# 03_pushswitch.net
KiCad netlist of a schematic drawn in Altium Designer
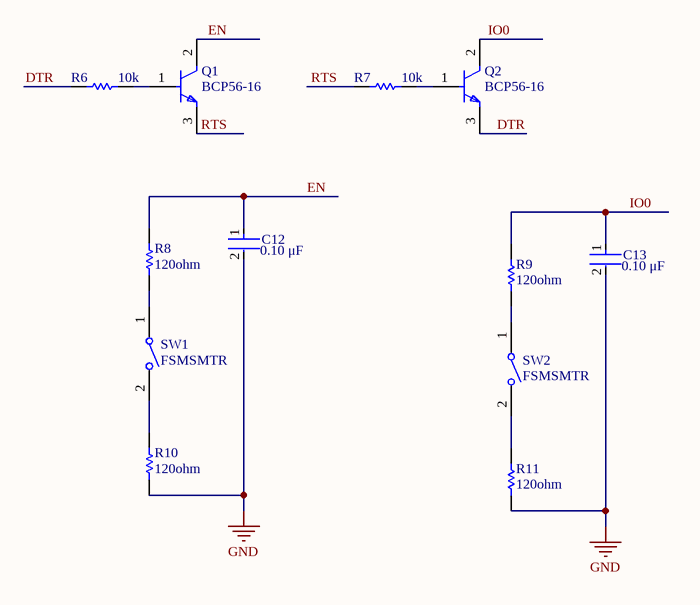
[diagram p0: 03_pushswitch.SchDoc]

(export (version "E")
  (design (tool "Eeschema 10.0.6"))
  (components
    (comp (ref "C12")
      (value "C0603C104M4RAC7411")
      (footprint "FP-C0603C-CF-MFG")
      (description "CAP CER 0.1UF 16V X7R 0603")
      (fields
        (field (name "TOLERANCE") "0.2")
        (field (name "CAPACITANCE") "0.10 μF")
        (field (name "MANUFACTURER") "KEMET")
      )
      (libsource (lib "Altium Content Vault") (part "b4654b650e69147ec39a6b967a45e02"))
    )
    (comp (ref "C13")
      (value "C0603C104M4RAC7411")
      (footprint "FP-C0603C-CF-MFG")
      (description "CAP CER 0.1UF 16V X7R 0603")
      (fields
        (field (name "TOLERANCE") "0.2")
        (field (name "CAPACITANCE") "0.10 μF")
        (field (name "MANUFACTURER") "KEMET")
      )
      (libsource (lib "Altium Content Vault") (part "b4654b650e69147ec39a6b967a45e02"))
    )
    (comp (ref "Q1")
      (value "BCP56-16")
      (footprint "FP-SOT-223-P008-MFG")
      (description "TRANS NPN 80V 1A SOT-223")
      (fields
        (field (name "OCTOPART") "https://octopart.com/bcp56-16-stmicroelectronics-13883839")
        (field (name "MANUFACTURER") "STMicroelectronics")
      )
      (libsource (lib "Altium Content Vault") (part "1c57d9dae74fe2702546667b0e849db"))
    )
    (comp (ref "Q2")
      (value "BCP56-16")
      (footprint "FP-SOT-223-P008-MFG")
      (description "TRANS NPN 80V 1A SOT-223")
      (fields
        (field (name "OCTOPART") "https://octopart.com/bcp56-16-stmicroelectronics-13883839")
        (field (name "MANUFACTURER") "STMicroelectronics")
      )
      (libsource (lib "Altium Content Vault") (part "1c57d9dae74fe2702546667b0e849db"))
    )
    (comp (ref "R6")
      (value "10k")
      (footprint "RESC1609X55X30LL15T15")
      (description "Chip Resistor, 10 KOhm, +/- 1%, 0.1 W, -55 to 155 degC, 0603 (1608 Metric), RoHS, Tape and Reel")
      (fields (field (name "TOLERANCE") "1%") (field (name "MANUFACTURER") "Panasonic"))
      (libsource (lib "Altium Content Vault") (part "RES-2"))
    )
    (comp (ref "R7")
      (value "10k")
      (footprint "RESC1609X55X30LL15T15")
      (description "Chip Resistor, 10 KOhm, +/- 1%, 0.1 W, -55 to 155 degC, 0603 (1608 Metric), RoHS, Tape and Reel")
      (fields (field (name "TOLERANCE") "1%") (field (name "MANUFACTURER") "Panasonic"))
      (libsource (lib "Altium Content Vault") (part "RES-2"))
    )
    (comp (ref "R8")
      (value "120ohm")
      (footprint "RESC1608X55X30NL20T20")
      (fields (field (name "PART NUMBER") "ERA-3AEB121V") (field (name "MANUFACTURER") "Panasonic"))
      (libsource (lib "Altium Content Vault") (part "RES"))
    )
    (comp (ref "R9")
      (value "120ohm")
      (footprint "RESC1608X55X30NL20T20")
      (fields (field (name "PART NUMBER") "ERA-3AEB121V") (field (name "MANUFACTURER") "Panasonic"))
      (libsource (lib "Altium Content Vault") (part "RES"))
    )
    (comp (ref "R10")
      (value "120ohm")
      (footprint "RESC1608X55X30NL20T20")
      (fields (field (name "PART NUMBER") "ERA-3AEB121V") (field (name "MANUFACTURER") "Panasonic"))
      (libsource (lib "Altium Content Vault") (part "RES"))
    )
    (comp (ref "R11")
      (value "120ohm")
      (footprint "RESC1608X55X30NL20T20")
      (fields (field (name "PART NUMBER") "ERA-3AEB121V") (field (name "MANUFACTURER") "Panasonic"))
      (libsource (lib "Altium Content Vault") (part "RES"))
    )
    (comp (ref "SW1")
      (value "FSMSMTR")
      (footprint "TECO-FSMSMTR_V")
      (description "FSMSM Push Button Switch, 50 mA, -35 to 85 degC, 2-Pin SMD, RoHS, Tape and Reel")
      (fields (field (name "MANUFACTURER") "TE Connectivity"))
      (libsource (lib "Altium Content Vault") (part "SW-SPST-2_C"))
    )
    (comp (ref "SW2")
      (value "FSMSMTR")
      (footprint "TECO-FSMSMTR_V")
      (description "FSMSM Push Button Switch, 50 mA, -35 to 85 degC, 2-Pin SMD, RoHS, Tape and Reel")
      (fields (field (name "MANUFACTURER") "TE Connectivity"))
      (libsource (lib "Altium Content Vault") (part "SW-SPST-2_C"))
    )
  )
  (nets
    (net (code "1") (name "/DTR") (class "Default")
      (node (ref "Q2") (pin "3") (pinfunction "E_3") (pintype "passive"))
      (node (ref "R6") (pin "1") (pinfunction "1_1") (pintype "passive"))
    )
    (net (code "2") (name "/EN") (class "Default")
      (node (ref "C12") (pin "1") (pinfunction "1_1") (pintype "passive"))
      (node (ref "Q1") (pin "2") (pinfunction "C_2") (pintype "passive"))
      (node (ref "R8") (pin "2") (pinfunction "2_2") (pintype "passive"))
    )
    (net (code "3") (name "/IO0") (class "Default")
      (node (ref "C13") (pin "1") (pinfunction "1_1") (pintype "passive"))
      (node (ref "Q2") (pin "2") (pinfunction "C_2") (pintype "passive"))
      (node (ref "R9") (pin "2") (pinfunction "2_2") (pintype "passive"))
    )
    (net (code "4") (name "/RTS") (class "Default")
      (node (ref "Q1") (pin "3") (pinfunction "E_3") (pintype "passive"))
      (node (ref "R7") (pin "1") (pinfunction "1_1") (pintype "passive"))
    )
    (net (code "5") (name "GND") (class "Default")
      (node (ref "C12") (pin "2") (pinfunction "2_2") (pintype "passive"))
      (node (ref "C13") (pin "2") (pinfunction "2_2") (pintype "passive"))
      (node (ref "R10") (pin "1") (pinfunction "1_1") (pintype "passive"))
      (node (ref "R11") (pin "1") (pinfunction "1_1") (pintype "passive"))
    )
    (net (code "6") (name "Net-(Q1-B)") (class "Default")
      (node (ref "Q1") (pin "1") (pinfunction "B_1") (pintype "passive"))
      (node (ref "R6") (pin "2") (pinfunction "2_2") (pintype "passive"))
    )
    (net (code "7") (name "Net-(Q2-B)") (class "Default")
      (node (ref "Q2") (pin "1") (pinfunction "B_1") (pintype "passive"))
      (node (ref "R7") (pin "2") (pinfunction "2_2") (pintype "passive"))
    )
    (net (code "8") (name "Net-(R8-Pad1)") (class "Default")
      (node (ref "R8") (pin "1") (pinfunction "1_1") (pintype "passive"))
      (node (ref "SW1") (pin "1") (pinfunction "1_1") (pintype "passive"))
    )
    (net (code "9") (name "Net-(R9-Pad1)") (class "Default")
      (node (ref "R9") (pin "1") (pinfunction "1_1") (pintype "passive"))
      (node (ref "SW2") (pin "1") (pinfunction "1_1") (pintype "passive"))
    )
    (net (code "10") (name "Net-(R10-Pad2)") (class "Default")
      (node (ref "R10") (pin "2") (pinfunction "2_2") (pintype "passive"))
      (node (ref "SW1") (pin "2") (pinfunction "2_2") (pintype "passive"))
    )
    (net (code "11") (name "Net-(R11-Pad2)") (class "Default")
      (node (ref "R11") (pin "2") (pinfunction "2_2") (pintype "passive"))
      (node (ref "SW2") (pin "2") (pinfunction "2_2") (pintype "passive"))
    )
  )
)
